# shield.net
KiCad netlist of a schematic drawn in EAGLE
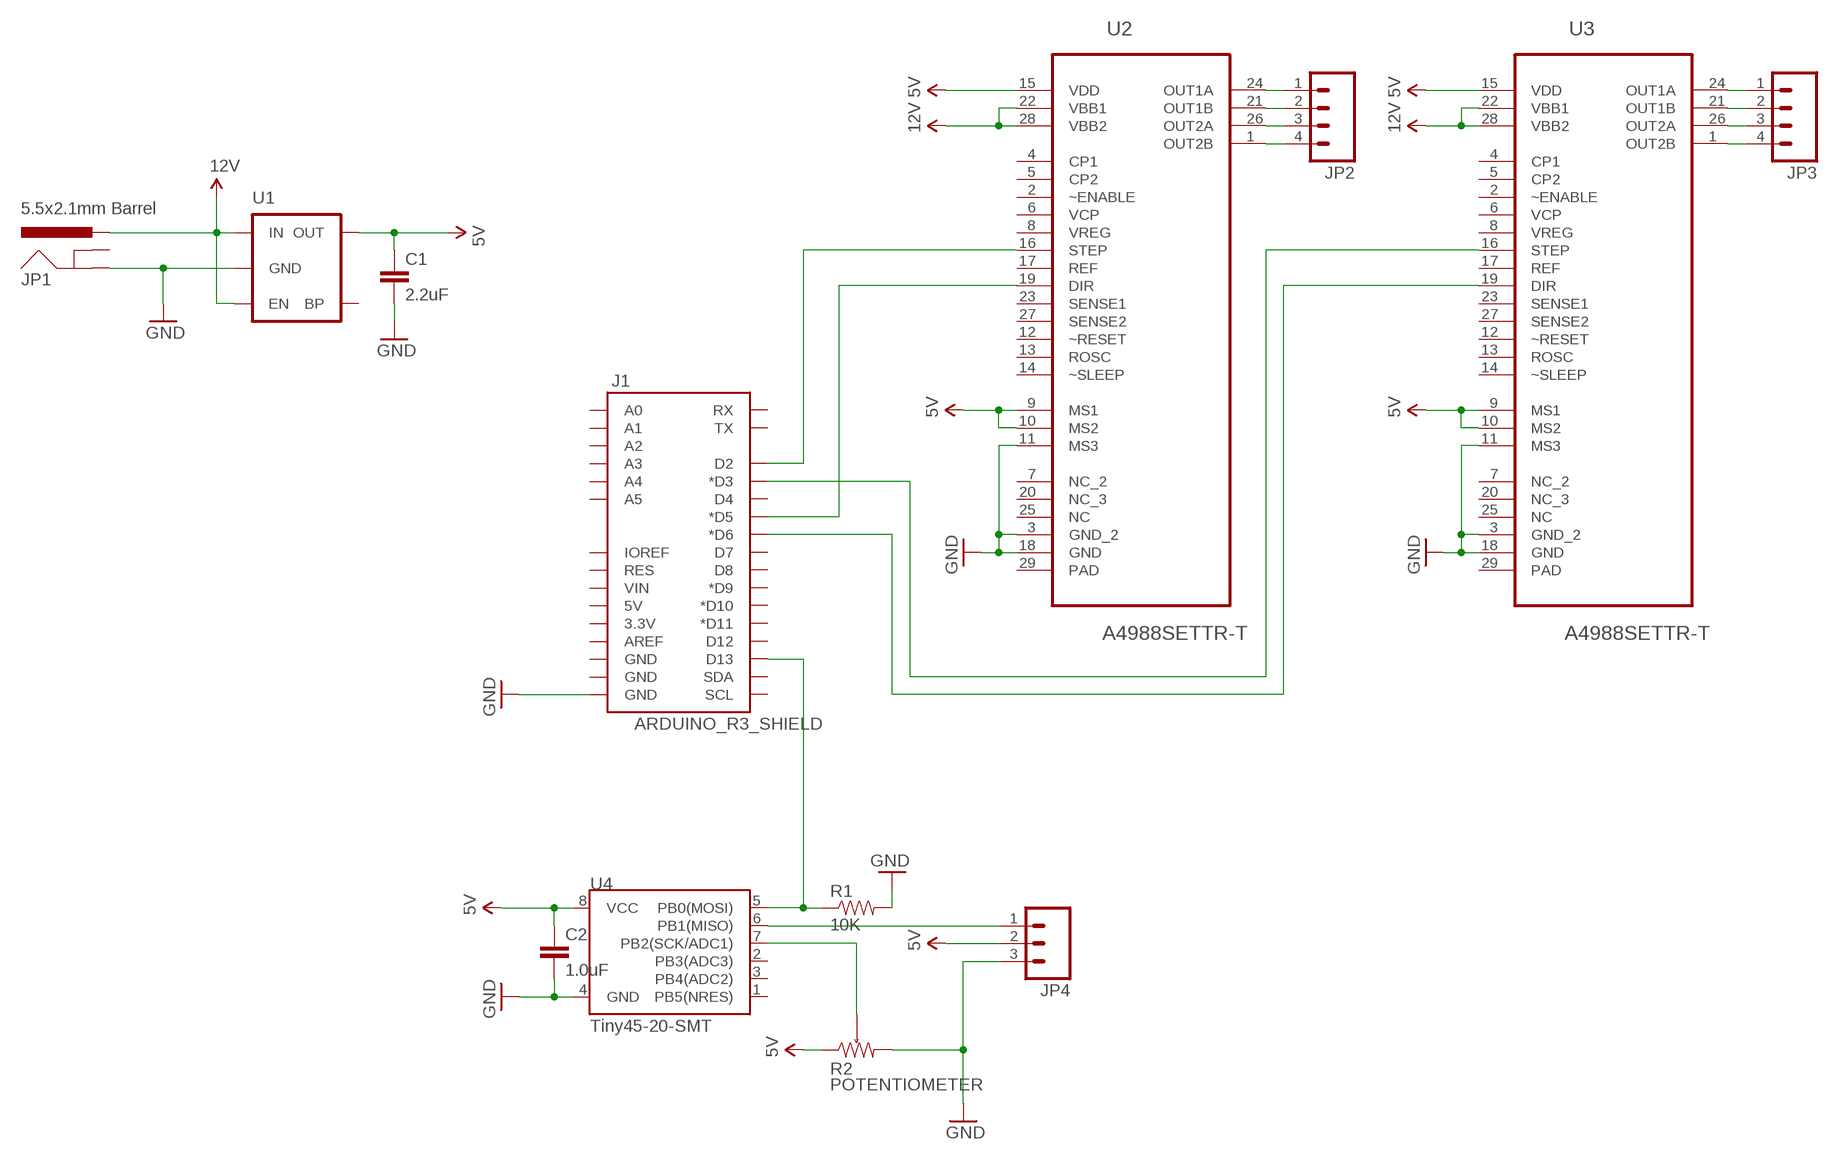
[diagram p0: schematic, sheet 1]

(export (version "E")
  (design (tool "Eeschema 10.0.6"))
  (components
    (comp (ref "C1")
      (value "2.2uF")
      (footprint "eagle-import:0805")
      (libsource (lib "eagle-import") (part "2.2UF-25V-+80/-20(0805)"))
    )
    (comp (ref "C2")
      (value "1.0uF")
      (footprint "eagle-import:0805")
      (libsource (lib "eagle-import") (part "1.0UF-25V-+80/-20(0805)"))
    )
    (comp (ref "J1")
      (value "ARDUINO_R3_SHIELD")
      (footprint "eagle-import:UNO_R3_SHIELD")
      (libsource (lib "eagle-import") (part "ARDUINO_R3_SHIELD"))
    )
    (comp (ref "JP1")
      (value "5.5x2.1mm Barrel")
      (footprint "eagle-import:POWER_JACK_SMD")
      (libsource (lib "eagle-import") (part "POWER_JACKSMD"))
    )
    (comp (ref "JP2")
      (value "M04SCREW")
      (footprint "eagle-import:SCREWTERMINAL-3.5MM-4")
      (libsource (lib "eagle-import") (part "M04SCREW"))
    )
    (comp (ref "JP3")
      (value "M04SCREW")
      (footprint "eagle-import:SCREWTERMINAL-3.5MM-4")
      (libsource (lib "eagle-import") (part "M04SCREW"))
    )
    (comp (ref "JP4")
      (value "M03SCREW")
      (footprint "eagle-import:SCREWTERMINAL-3.5MM-3")
      (libsource (lib "eagle-import") (part "M03SCREW"))
    )
    (comp (ref "R1")
      (value "10K")
      (footprint "eagle-import:0603-RES")
      (libsource (lib "eagle-import") (part "10KOHM-1/10W-1%(0603)0603"))
    )
    (comp (ref "R2")
      (value "POTENTIOMETER")
      (footprint "eagle-import:0603-ARV")
      (libsource (lib "eagle-import") (part "POTENTIOMETER"))
    )
    (comp (ref "U1")
      (value "MIC52055V")
      (footprint "eagle-import:SOT23-5")
      (libsource (lib "eagle-import") (part "MIC52055V"))
    )
    (comp (ref "U2")
      (value "A4988SETTR-T")
      (footprint "eagle-import:QFN50P500X500X100-29N")
      (libsource (lib "eagle-import") (part "A4988SETTR-T"))
    )
    (comp (ref "U3")
      (value "A4988SETTR-T")
      (footprint "eagle-import:QFN50P500X500X100-29N")
      (libsource (lib "eagle-import") (part "A4988SETTR-T"))
    )
    (comp (ref "U4")
      (value "Tiny45-20-SMT")
      (footprint "eagle-import:SO08-EIAJ")
      (libsource (lib "eagle-import") (part "ATTINY45TINY45-20-SMT"))
    )
  )
  (nets
    (net (code "1") (name "5V") (class "Default")
      (node (ref "C1") (pin "1") (pinfunction "1_1") (pintype "passive"))
      (node (ref "C2") (pin "1") (pinfunction "1_1") (pintype "passive"))
      (node (ref "JP4") (pin "2") (pinfunction "2_2") (pintype "passive"))
      (node (ref "R2") (pin "1") (pinfunction "1_1") (pintype "passive"))
      (node (ref "U1") (pin "5") (pinfunction "OUT_5") (pintype "passive"))
      (node (ref "U2") (pin "10") (pinfunction "MS2_10") (pintype "input"))
      (node (ref "U2") (pin "15") (pinfunction "VDD_15") (pintype "power_in"))
      (node (ref "U2") (pin "9") (pinfunction "MS1_9") (pintype "input"))
      (node (ref "U3") (pin "10") (pinfunction "MS2_10") (pintype "input"))
      (node (ref "U3") (pin "15") (pinfunction "VDD_15") (pintype "power_in"))
      (node (ref "U3") (pin "9") (pinfunction "MS1_9") (pintype "input"))
      (node (ref "U4") (pin "8") (pinfunction "VCC_8") (pintype "bidirectional"))
    )
    (net (code "2") (name "12V") (class "Default")
      (node (ref "JP1") (pin "VIN0") (pinfunction "PWR_VIN0") (pintype "bidirectional"))
      (node (ref "U1") (pin "1") (pinfunction "IN_1") (pintype "input"))
      (node (ref "U1") (pin "3") (pinfunction "EN_3") (pintype "input"))
      (node (ref "U2") (pin "22") (pinfunction "VBB1_22") (pintype "power_in"))
      (node (ref "U2") (pin "28") (pinfunction "VBB2_28") (pintype "power_in"))
      (node (ref "U3") (pin "22") (pinfunction "VBB1_22") (pintype "power_in"))
      (node (ref "U3") (pin "28") (pinfunction "VBB2_28") (pintype "power_in"))
    )
    (net (code "3") (name "GND") (class "Default")
      (node (ref "C1") (pin "2") (pinfunction "2_2") (pintype "passive"))
      (node (ref "C2") (pin "2") (pinfunction "2_2") (pintype "passive"))
      (node (ref "J1") (pin "GND@0") (pinfunction "GND_GND@0") (pintype "bidirectional"))
      (node (ref "JP1") (pin "P$4") (pinfunction "GND_P$4") (pintype "bidirectional"))
      (node (ref "JP4") (pin "3") (pinfunction "3_3") (pintype "passive"))
      (node (ref "R1") (pin "2") (pinfunction "2_2") (pintype "passive"))
      (node (ref "R2") (pin "2") (pinfunction "2_2") (pintype "passive"))
      (node (ref "U1") (pin "2") (pinfunction "GND_2") (pintype "input"))
      (node (ref "U2") (pin "11") (pinfunction "MS3_11") (pintype "input"))
      (node (ref "U2") (pin "18") (pinfunction "GND_18") (pintype "passive"))
      (node (ref "U2") (pin "3") (pinfunction "GND_2_3") (pintype "passive"))
      (node (ref "U3") (pin "11") (pinfunction "MS3_11") (pintype "input"))
      (node (ref "U3") (pin "18") (pinfunction "GND_18") (pintype "passive"))
      (node (ref "U3") (pin "3") (pinfunction "GND_2_3") (pintype "passive"))
      (node (ref "U4") (pin "4") (pinfunction "GND_4") (pintype "bidirectional"))
    )
    (net (code "4") (name "Net-(J1-*D3)") (class "Default")
      (node (ref "J1") (pin "D3") (pinfunction "*D3_D3") (pintype "bidirectional"))
      (node (ref "U3") (pin "16") (pinfunction "STEP_16") (pintype "input"))
    )
    (net (code "5") (name "Net-(J1-*D5)") (class "Default")
      (node (ref "J1") (pin "D5") (pinfunction "*D5_D5") (pintype "bidirectional"))
      (node (ref "U2") (pin "19") (pinfunction "DIR_19") (pintype "input"))
    )
    (net (code "6") (name "Net-(J1-*D6)") (class "Default")
      (node (ref "J1") (pin "D6") (pinfunction "*D6_D6") (pintype "bidirectional"))
      (node (ref "U3") (pin "19") (pinfunction "DIR_19") (pintype "input"))
    )
    (net (code "7") (name "Net-(U2-OUT1A)") (class "Default")
      (node (ref "JP2") (pin "1") (pinfunction "1_1") (pintype "passive"))
      (node (ref "U2") (pin "24") (pinfunction "OUT1A_24") (pintype "output"))
    )
    (net (code "8") (name "Net-(U2-OUT1B)") (class "Default")
      (node (ref "JP2") (pin "2") (pinfunction "2_2") (pintype "passive"))
      (node (ref "U2") (pin "21") (pinfunction "OUT1B_21") (pintype "output"))
    )
    (net (code "9") (name "Net-(U2-OUT2A)") (class "Default")
      (node (ref "JP2") (pin "3") (pinfunction "3_3") (pintype "passive"))
      (node (ref "U2") (pin "26") (pinfunction "OUT2A_26") (pintype "output"))
    )
    (net (code "10") (name "Net-(U2-OUT2B)") (class "Default")
      (node (ref "JP2") (pin "4") (pinfunction "4_4") (pintype "passive"))
      (node (ref "U2") (pin "1") (pinfunction "OUT2B_1") (pintype "output"))
    )
    (net (code "11") (name "Net-(U2-STEP)") (class "Default")
      (node (ref "J1") (pin "D2") (pinfunction "D2_D2") (pintype "bidirectional"))
      (node (ref "U2") (pin "16") (pinfunction "STEP_16") (pintype "input"))
    )
    (net (code "12") (name "Net-(U3-OUT1A)") (class "Default")
      (node (ref "JP3") (pin "1") (pinfunction "1_1") (pintype "passive"))
      (node (ref "U3") (pin "24") (pinfunction "OUT1A_24") (pintype "output"))
    )
    (net (code "13") (name "Net-(U3-OUT1B)") (class "Default")
      (node (ref "JP3") (pin "2") (pinfunction "2_2") (pintype "passive"))
      (node (ref "U3") (pin "21") (pinfunction "OUT1B_21") (pintype "output"))
    )
    (net (code "14") (name "Net-(U3-OUT2A)") (class "Default")
      (node (ref "JP3") (pin "3") (pinfunction "3_3") (pintype "passive"))
      (node (ref "U3") (pin "26") (pinfunction "OUT2A_26") (pintype "output"))
    )
    (net (code "15") (name "Net-(U3-OUT2B)") (class "Default")
      (node (ref "JP3") (pin "4") (pinfunction "4_4") (pintype "passive"))
      (node (ref "U3") (pin "1") (pinfunction "OUT2B_1") (pintype "output"))
    )
    (net (code "16") (name "Net-(U4-PB0(MOSI))") (class "Default")
      (node (ref "J1") (pin "D13") (pinfunction "D13_D13") (pintype "bidirectional"))
      (node (ref "R1") (pin "1") (pinfunction "1_1") (pintype "passive"))
      (node (ref "U4") (pin "5") (pinfunction "PB0(MOSI)_5") (pintype "bidirectional"))
    )
    (net (code "17") (name "Net-(U4-PB1(MISO))") (class "Default")
      (node (ref "JP4") (pin "1") (pinfunction "1_1") (pintype "passive"))
      (node (ref "U4") (pin "6") (pinfunction "PB1(MISO)_6") (pintype "bidirectional"))
    )
    (net (code "18") (name "Net-(U4-PB2(SCK{slash}ADC1))") (class "Default")
      (node (ref "R2") (pin "3") (pinfunction "P$1_3") (pintype "bidirectional"))
      (node (ref "R2") (pin "4") (pinfunction "P$1_4") (pintype "bidirectional"))
      (node (ref "R2") (pin "5") (pinfunction "P$1_5") (pintype "bidirectional"))
      (node (ref "R2") (pin "6") (pinfunction "P$1_6") (pintype "bidirectional"))
      (node (ref "R2") (pin "7") (pinfunction "P$1_7") (pintype "bidirectional"))
      (node (ref "R2") (pin "8") (pinfunction "P$1_8") (pintype "bidirectional"))
      (node (ref "U4") (pin "7") (pinfunction "PB2(SCK/ADC1)_7") (pintype "bidirectional"))
    )
    (net (code "19") (name "unconnected-(J1-*D9-PadD9)") (class "Default")
      (node (ref "J1") (pin "D9") (pinfunction "*D9_D9") (pintype "bidirectional"))
    )
    (net (code "20") (name "unconnected-(J1-*D10-PadD10)") (class "Default")
      (node (ref "J1") (pin "D10") (pinfunction "*D10_D10") (pintype "bidirectional"))
    )
    (net (code "21") (name "unconnected-(J1-*D11-PadD11)") (class "Default")
      (node (ref "J1") (pin "D11") (pinfunction "*D11_D11") (pintype "bidirectional"))
    )
    (net (code "22") (name "unconnected-(J1-GND-PadGND@1)") (class "Default")
      (node (ref "J1") (pin "GND@1") (pinfunction "GND_GND@1") (pintype "bidirectional"))
    )
    (net (code "23") (name "unconnected-(J1-GND-PadGND@2)") (class "Default")
      (node (ref "J1") (pin "GND@2") (pinfunction "GND_GND@2") (pintype "bidirectional"))
    )
    (net (code "24") (name "unconnected-(J1-Pad3.3V)") (class "Default")
      (node (ref "J1") (pin "3.3V") (pinfunction "3.3V_3.3V") (pintype "bidirectional"))
    )
    (net (code "25") (name "unconnected-(J1-Pad5V)") (class "Default")
      (node (ref "J1") (pin "5V") (pinfunction "5V_5V") (pintype "bidirectional"))
    )
    (net (code "26") (name "unconnected-(J1-PadA0)") (class "Default")
      (node (ref "J1") (pin "A0") (pinfunction "A0_A0") (pintype "bidirectional"))
    )
    (net (code "27") (name "unconnected-(J1-PadA1)") (class "Default")
      (node (ref "J1") (pin "A1") (pinfunction "A1_A1") (pintype "bidirectional"))
    )
    (net (code "28") (name "unconnected-(J1-PadA2)") (class "Default")
      (node (ref "J1") (pin "A2") (pinfunction "A2_A2") (pintype "bidirectional"))
    )
    (net (code "29") (name "unconnected-(J1-PadA3)") (class "Default")
      (node (ref "J1") (pin "A3") (pinfunction "A3_A3") (pintype "bidirectional"))
    )
    (net (code "30") (name "unconnected-(J1-PadA4)") (class "Default")
      (node (ref "J1") (pin "A4") (pinfunction "A4_A4") (pintype "bidirectional"))
    )
    (net (code "31") (name "unconnected-(J1-PadA5)") (class "Default")
      (node (ref "J1") (pin "A5") (pinfunction "A5_A5") (pintype "bidirectional"))
    )
    (net (code "32") (name "unconnected-(J1-PadAREF)") (class "Default")
      (node (ref "J1") (pin "AREF") (pinfunction "AREF_AREF") (pintype "bidirectional"))
    )
    (net (code "33") (name "unconnected-(J1-PadD4)") (class "Default")
      (node (ref "J1") (pin "D4") (pinfunction "D4_D4") (pintype "bidirectional"))
    )
    (net (code "34") (name "unconnected-(J1-PadD7)") (class "Default")
      (node (ref "J1") (pin "D7") (pinfunction "D7_D7") (pintype "bidirectional"))
    )
    (net (code "35") (name "unconnected-(J1-PadD8)") (class "Default")
      (node (ref "J1") (pin "D8") (pinfunction "D8_D8") (pintype "bidirectional"))
    )
    (net (code "36") (name "unconnected-(J1-PadD12)") (class "Default")
      (node (ref "J1") (pin "D12") (pinfunction "D12_D12") (pintype "bidirectional"))
    )
    (net (code "37") (name "unconnected-(J1-PadIOREF)") (class "Default")
      (node (ref "J1") (pin "IOREF") (pinfunction "IOREF_IOREF") (pintype "bidirectional"))
    )
    (net (code "38") (name "unconnected-(J1-PadRES)") (class "Default")
      (node (ref "J1") (pin "RES") (pinfunction "RES_RES") (pintype "bidirectional"))
    )
    (net (code "39") (name "unconnected-(J1-PadRX)") (class "Default")
      (node (ref "J1") (pin "RX") (pinfunction "RX_RX") (pintype "bidirectional"))
    )
    (net (code "40") (name "unconnected-(J1-PadSCL)") (class "Default")
      (node (ref "J1") (pin "SCL") (pinfunction "SCL_SCL") (pintype "bidirectional"))
    )
    (net (code "41") (name "unconnected-(J1-PadSDA)") (class "Default")
      (node (ref "J1") (pin "SDA") (pinfunction "SDA_SDA") (pintype "bidirectional"))
    )
    (net (code "42") (name "unconnected-(J1-PadTX)") (class "Default")
      (node (ref "J1") (pin "TX") (pinfunction "TX_TX") (pintype "bidirectional"))
    )
    (net (code "43") (name "unconnected-(J1-PadVIN)") (class "Default")
      (node (ref "J1") (pin "VIN") (pinfunction "VIN_VIN") (pintype "bidirectional"))
    )
    (net (code "44") (name "unconnected-(JP1-GNDBREAK-PadGND)") (class "Default")
      (node (ref "JP1") (pin "GND") (pinfunction "GNDBREAK_GND") (pintype "bidirectional"))
    )
    (net (code "45") (name "unconnected-(U1-BP-Pad4)") (class "Default")
      (node (ref "U1") (pin "4") (pinfunction "BP_4") (pintype "input"))
    )
    (net (code "46") (name "unconnected-(U2-CP1-Pad4)") (class "Default")
      (node (ref "U2") (pin "4") (pinfunction "CP1_4") (pintype "passive"))
    )
    (net (code "47") (name "unconnected-(U2-CP2-Pad5)") (class "Default")
      (node (ref "U2") (pin "5") (pinfunction "CP2_5") (pintype "passive"))
    )
    (net (code "48") (name "unconnected-(U2-NC-Pad25)") (class "Default")
      (node (ref "U2") (pin "25") (pinfunction "NC_25") (pintype "no_connect"))
    )
    (net (code "49") (name "unconnected-(U2-NC_2-Pad7)") (class "Default")
      (node (ref "U2") (pin "7") (pinfunction "NC_2_7") (pintype "no_connect"))
    )
    (net (code "50") (name "unconnected-(U2-NC_3-Pad20)") (class "Default")
      (node (ref "U2") (pin "20") (pinfunction "NC_3_20") (pintype "no_connect"))
    )
    (net (code "51") (name "unconnected-(U2-PAD-Pad29)") (class "Default")
      (node (ref "U2") (pin "29") (pinfunction "PAD_29") (pintype "passive"))
    )
    (net (code "52") (name "unconnected-(U2-REF-Pad17)") (class "Default")
      (node (ref "U2") (pin "17") (pinfunction "REF_17") (pintype "input"))
    )
    (net (code "53") (name "unconnected-(U2-ROSC-Pad13)") (class "Default")
      (node (ref "U2") (pin "13") (pinfunction "ROSC_13") (pintype "input"))
    )
    (net (code "54") (name "unconnected-(U2-SENSE1-Pad23)") (class "Default")
      (node (ref "U2") (pin "23") (pinfunction "SENSE1_23") (pintype "input"))
    )
    (net (code "55") (name "unconnected-(U2-SENSE2-Pad27)") (class "Default")
      (node (ref "U2") (pin "27") (pinfunction "SENSE2_27") (pintype "input"))
    )
    (net (code "56") (name "unconnected-(U2-VCP-Pad6)") (class "Default")
      (node (ref "U2") (pin "6") (pinfunction "VCP_6") (pintype "passive"))
    )
    (net (code "57") (name "unconnected-(U2-VREG-Pad8)") (class "Default")
      (node (ref "U2") (pin "8") (pinfunction "VREG_8") (pintype "passive"))
    )
    (net (code "58") (name "unconnected-(U2-~{ENABLE}-Pad2)") (class "Default")
      (node (ref "U2") (pin "2") (pinfunction "~{ENABLE}_2") (pintype "input"))
    )
    (net (code "59") (name "unconnected-(U2-~{RESET}-Pad12)") (class "Default")
      (node (ref "U2") (pin "12") (pinfunction "~{RESET}_12") (pintype "input"))
    )
    (net (code "60") (name "unconnected-(U2-~{SLEEP}-Pad14)") (class "Default")
      (node (ref "U2") (pin "14") (pinfunction "~{SLEEP}_14") (pintype "input"))
    )
    (net (code "61") (name "unconnected-(U3-CP1-Pad4)") (class "Default")
      (node (ref "U3") (pin "4") (pinfunction "CP1_4") (pintype "passive"))
    )
    (net (code "62") (name "unconnected-(U3-CP2-Pad5)") (class "Default")
      (node (ref "U3") (pin "5") (pinfunction "CP2_5") (pintype "passive"))
    )
    (net (code "63") (name "unconnected-(U3-NC-Pad25)") (class "Default")
      (node (ref "U3") (pin "25") (pinfunction "NC_25") (pintype "no_connect"))
    )
    (net (code "64") (name "unconnected-(U3-NC_2-Pad7)") (class "Default")
      (node (ref "U3") (pin "7") (pinfunction "NC_2_7") (pintype "no_connect"))
    )
    (net (code "65") (name "unconnected-(U3-NC_3-Pad20)") (class "Default")
      (node (ref "U3") (pin "20") (pinfunction "NC_3_20") (pintype "no_connect"))
    )
    (net (code "66") (name "unconnected-(U3-PAD-Pad29)") (class "Default")
      (node (ref "U3") (pin "29") (pinfunction "PAD_29") (pintype "passive"))
    )
    (net (code "67") (name "unconnected-(U3-REF-Pad17)") (class "Default")
      (node (ref "U3") (pin "17") (pinfunction "REF_17") (pintype "input"))
    )
    (net (code "68") (name "unconnected-(U3-ROSC-Pad13)") (class "Default")
      (node (ref "U3") (pin "13") (pinfunction "ROSC_13") (pintype "input"))
    )
    (net (code "69") (name "unconnected-(U3-SENSE1-Pad23)") (class "Default")
      (node (ref "U3") (pin "23") (pinfunction "SENSE1_23") (pintype "input"))
    )
    (net (code "70") (name "unconnected-(U3-SENSE2-Pad27)") (class "Default")
      (node (ref "U3") (pin "27") (pinfunction "SENSE2_27") (pintype "input"))
    )
    (net (code "71") (name "unconnected-(U3-VCP-Pad6)") (class "Default")
      (node (ref "U3") (pin "6") (pinfunction "VCP_6") (pintype "passive"))
    )
    (net (code "72") (name "unconnected-(U3-VREG-Pad8)") (class "Default")
      (node (ref "U3") (pin "8") (pinfunction "VREG_8") (pintype "passive"))
    )
    (net (code "73") (name "unconnected-(U3-~{ENABLE}-Pad2)") (class "Default")
      (node (ref "U3") (pin "2") (pinfunction "~{ENABLE}_2") (pintype "input"))
    )
    (net (code "74") (name "unconnected-(U3-~{RESET}-Pad12)") (class "Default")
      (node (ref "U3") (pin "12") (pinfunction "~{RESET}_12") (pintype "input"))
    )
    (net (code "75") (name "unconnected-(U3-~{SLEEP}-Pad14)") (class "Default")
      (node (ref "U3") (pin "14") (pinfunction "~{SLEEP}_14") (pintype "input"))
    )
    (net (code "76") (name "unconnected-(U4-PB3(ADC3)-Pad2)") (class "Default")
      (node (ref "U4") (pin "2") (pinfunction "PB3(ADC3)_2") (pintype "bidirectional"))
    )
    (net (code "77") (name "unconnected-(U4-PB4(ADC2)-Pad3)") (class "Default")
      (node (ref "U4") (pin "3") (pinfunction "PB4(ADC2)_3") (pintype "bidirectional"))
    )
    (net (code "78") (name "unconnected-(U4-PB5(NRES)-Pad1)") (class "Default")
      (node (ref "U4") (pin "1") (pinfunction "PB5(NRES)_1") (pintype "bidirectional"))
    )
  )
)
